# CH32V203K6T6-R0.net
KiCad netlist of a schematic drawn in Altium Designer
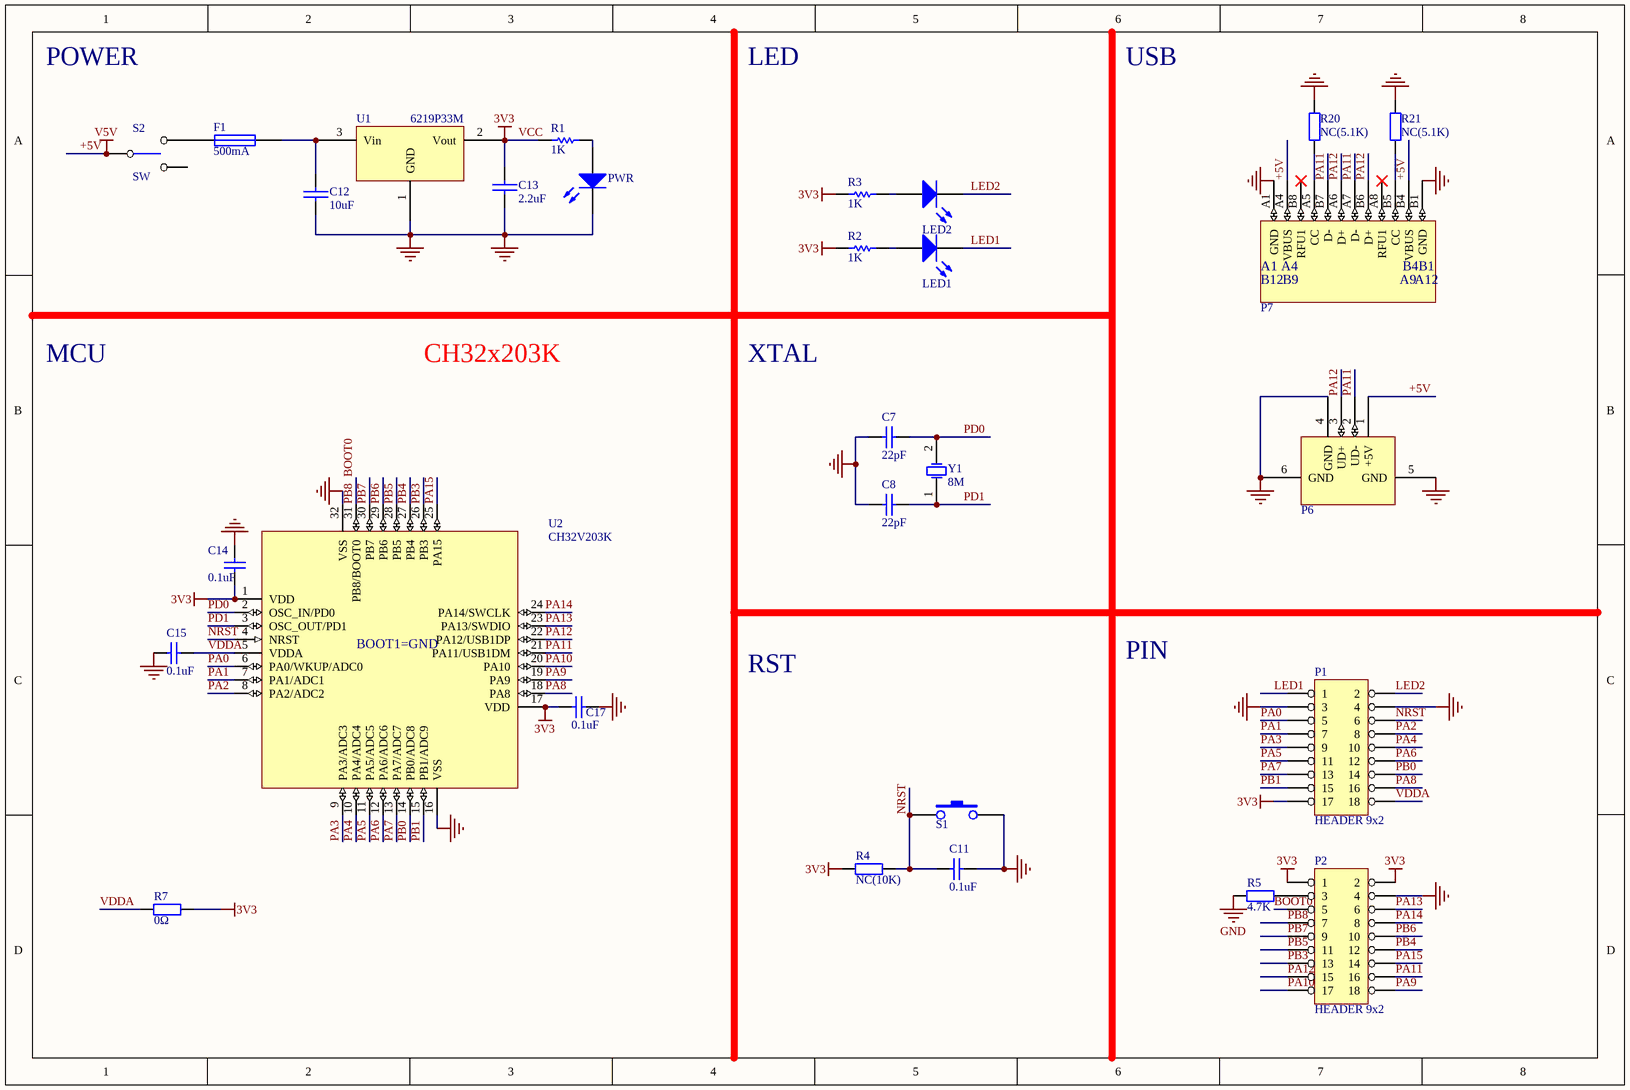
[diagram p0: CH32V203K6T6-R0.SchDoc]

(export (version "E")
  (design (tool "Eeschema 10.0.6"))
  (components
    (comp (ref "C7")
      (value "22pF")
      (footprint "0603_C")
      (description "Capacitor")
      (fields (field (name "PUBLISHER") "Altium Limited"))
      (libsource (lib "*") (part "Cap"))
    )
    (comp (ref "C8")
      (value "22pF")
      (footprint "0603_C")
      (description "Capacitor")
      (fields (field (name "PUBLISHER") "Altium Limited"))
      (libsource (lib "*") (part "Cap"))
    )
    (comp (ref "C11")
      (value "0.1uF")
      (footprint "0603_C")
      (description "Capacitor")
      (fields (field (name "PUBLISHER") "Altium Limited"))
      (libsource (lib "*") (part "Cap"))
    )
    (comp (ref "C12")
      (value "10uF")
      (footprint "3216_C")
      (description "Capacitor")
      (libsource (lib "wch_sch_others") (part "CAP"))
    )
    (comp (ref "C13")
      (value "2.2uF")
      (footprint "0603_C")
      (description "Capacitor")
      (libsource (lib "wch_sch_others") (part "CAP"))
    )
    (comp (ref "C14")
      (value "0.1uF")
      (footprint "0603_C")
      (description "Capacitor")
      (fields (field (name "PUBLISHER") "Altium Limited"))
      (libsource (lib "*") (part "Cap"))
    )
    (comp (ref "C15")
      (value "0.1uF")
      (footprint "0603_C")
      (description "Capacitor")
      (fields (field (name "PUBLISHER") "Altium Limited"))
      (libsource (lib "*") (part "Cap"))
    )
    (comp (ref "C17")
      (value "0.1uF")
      (footprint "0603_C")
      (description "Capacitor")
      (fields (field (name "PUBLISHER") "Altium Limited"))
      (libsource (lib "*") (part "Cap"))
    )
    (comp (ref "F1")
      (value "500mA")
      (footprint "0603")
      (description "Fuse")
      (libsource (lib "*") (part "FUSE1"))
    )
    (comp (ref "LED1")
      (value "LED1   blue")
      (footprint "0603+")
      (description "Typical INFRARED GaAs LED")
      (fields (field (name "PUBLISHER") "Altium Limited"))
      (libsource (lib "*") (part "LED0"))
    )
    (comp (ref "LED2")
      (value "LED2  blue")
      (footprint "0603+")
      (description "Typical INFRARED GaAs LED")
      (fields (field (name "PUBLISHER") "Altium Limited"))
      (libsource (lib "*") (part "LED0"))
    )
    (comp (ref "P1")
      (value "HEADER 9x2")
      (footprint "MYPCB:IDC18-2.54MM")
      (description "Header, 9-Pin, Dual row")
      (libsource (lib "wch_sch_others") (part "HEADER 9x2"))
    )
    (comp (ref "P2")
      (value "HEADER 9x2")
      (footprint "MYPCB:IDC18-2.54MM")
      (description "Header, 9-Pin, Dual row")
      (libsource (lib "wch_sch_others") (part "HEADER 9x2"))
    )
    (comp (ref "P6")
      (value "USB_A")
      (footprint "USBAF")
      (description "USB Port")
      (libsource (lib "*") (part "USB"))
    )
    (comp (ref "P7")
      (value "TYPE-C")
      (footprint "TYPE-C-Receptacle-2.0")
      (libsource (lib "*") (part "TYPE-C1"))
    )
    (comp (ref "PWR")
      (value "POWER  red")
      (footprint "0603+")
      (description "Typical INFRARED GaAs LED")
      (fields (field (name "PUBLISHER") "Altium Limited"))
      (libsource (lib "*") (part "LED0"))
    )
    (comp (ref "R1")
      (value "1K")
      (footprint "0603")
      (description "Semiconductor Resistor")
      (fields (field (name "PUBLISHER") "Altium Limited"))
      (libsource (lib "*") (part "Res Semi"))
    )
    (comp (ref "R2")
      (value "1K")
      (footprint "0603")
      (description "Semiconductor Resistor")
      (fields (field (name "PUBLISHER") "Altium Limited"))
      (libsource (lib "*") (part "Res Semi"))
    )
    (comp (ref "R3")
      (value "1K")
      (footprint "0603")
      (description "Semiconductor Resistor")
      (fields (field (name "PUBLISHER") "Altium Limited"))
      (libsource (lib "*") (part "Res Semi"))
    )
    (comp (ref "R4")
      (value "NC(10K)")
      (footprint "0603")
      (description "Resistor")
      (fields (field (name "PUBLISHER") "Altium Limited"))
      (libsource (lib "") (part "Res2_1"))
    )
    (comp (ref "R5")
      (value "4.7K")
      (footprint "0603")
      (description "Resistor")
      (fields (field (name "PUBLISHER") "Altium Limited"))
      (libsource (lib "*") (part "Res2"))
    )
    (comp (ref "R7")
      (value "0Ω")
      (footprint "0603")
      (description "Resistor")
      (fields (field (name "PUBLISHER") "Altium Limited"))
      (libsource (lib "") (part "Res2_1"))
    )
    (comp (ref "R20")
      (value "NC(5.1K)")
      (footprint "0603")
      (description "Resistor")
      (libsource (lib "Miscellaneous Devices") (part "Res2"))
    )
    (comp (ref "R21")
      (value "NC(5.1K)")
      (footprint "0603")
      (description "Resistor")
      (libsource (lib "Miscellaneous Devices") (part "Res2"))
    )
    (comp (ref "S1") (value "RST") (footprint "SMD_6.1x3.65x2.5mm-KEY") (libsource (lib "*") (part "KEY")))
    (comp (ref "S2") (value "SW") (footprint "KEY2") (libsource (lib "*") (part "SW")))
    (comp (ref "U1")
      (value "6219P33M")
      (footprint "SOT-23")
      (libsource (lib "wch_sch_others") (part "6219P33M"))
    )
    (comp (ref "U2")
      (value "CH32V203K")
      (footprint "LQFP32")
      (description "RISC-V LMD-MCU, 144MHz, USB FS, CAN")
      (libsource (lib "CHXXX") (part "CH32V203K"))
    )
    (comp (ref "Y1")
      (value "8M")
      (footprint "XT_AT49")
      (description "Crystal Oscillator")
      (fields (field (name "PUBLISHER") "Altium Limited"))
      (libsource (lib "*") (part "XTAL"))
    )
  )
  (nets
    (net (code "2") (name "/BOOT0") (class "Default")
      (node (ref "P2") (pin "5") (pinfunction "5_5") (pintype "passive"))
      (node (ref "P2") (pin "7") (pinfunction "7_7") (pintype "passive"))
      (node (ref "U2") (pin "31") (pinfunction "PB8/BOOT0_31") (pintype "bidirectional"))
    )
    (net (code "3") (name "/LED1") (class "Default")
      (node (ref "LED1") (pin "2") (pinfunction "K_2") (pintype "passive"))
      (node (ref "P1") (pin "1") (pinfunction "1_1") (pintype "passive"))
    )
    (net (code "4") (name "/LED2") (class "Default")
      (node (ref "LED2") (pin "2") (pinfunction "K_2") (pintype "passive"))
      (node (ref "P1") (pin "2") (pinfunction "2_2") (pintype "passive"))
    )
    (net (code "5") (name "/NRST") (class "Default")
      (node (ref "C11") (pin "2") (pinfunction "2_2") (pintype "passive"))
      (node (ref "P1") (pin "6") (pinfunction "6_6") (pintype "passive"))
      (node (ref "R4") (pin "1") (pinfunction "1_1") (pintype "passive"))
      (node (ref "S1") (pin "1") (pinfunction "1_1") (pintype "passive"))
      (node (ref "U2") (pin "4") (pinfunction "NRST_4") (pintype "input"))
    )
    (net (code "6") (name "/PA0") (class "Default")
      (node (ref "P1") (pin "5") (pinfunction "5_5") (pintype "passive"))
      (node (ref "U2") (pin "6") (pinfunction "PA0/WKUP/ADC0_6") (pintype "bidirectional"))
    )
    (net (code "7") (name "/PA1") (class "Default")
      (node (ref "P1") (pin "7") (pinfunction "7_7") (pintype "passive"))
      (node (ref "U2") (pin "7") (pinfunction "PA1/ADC1_7") (pintype "bidirectional"))
    )
    (net (code "8") (name "/PA2") (class "Default")
      (node (ref "P1") (pin "8") (pinfunction "8_8") (pintype "passive"))
      (node (ref "U2") (pin "8") (pinfunction "PA2/ADC2_8") (pintype "bidirectional"))
    )
    (net (code "9") (name "/PA3") (class "Default")
      (node (ref "P1") (pin "9") (pinfunction "9_9") (pintype "passive"))
      (node (ref "U2") (pin "9") (pinfunction "PA3/ADC3_9") (pintype "bidirectional"))
    )
    (net (code "10") (name "/PA4") (class "Default")
      (node (ref "P1") (pin "10") (pinfunction "10_10") (pintype "passive"))
      (node (ref "U2") (pin "10") (pinfunction "PA4/ADC4_10") (pintype "bidirectional"))
    )
    (net (code "11") (name "/PA5") (class "Default")
      (node (ref "P1") (pin "11") (pinfunction "11_11") (pintype "passive"))
      (node (ref "U2") (pin "11") (pinfunction "PA5/ADC5_11") (pintype "bidirectional"))
    )
    (net (code "12") (name "/PA6") (class "Default")
      (node (ref "P1") (pin "12") (pinfunction "12_12") (pintype "passive"))
      (node (ref "U2") (pin "12") (pinfunction "PA6/ADC6_12") (pintype "bidirectional"))
    )
    (net (code "13") (name "/PA7") (class "Default")
      (node (ref "P1") (pin "13") (pinfunction "13_13") (pintype "passive"))
      (node (ref "U2") (pin "13") (pinfunction "PA7/ADC7_13") (pintype "bidirectional"))
    )
    (net (code "14") (name "/PA8") (class "Default")
      (node (ref "P1") (pin "16") (pinfunction "16_16") (pintype "passive"))
      (node (ref "U2") (pin "18") (pinfunction "PA8_18") (pintype "bidirectional"))
    )
    (net (code "15") (name "/PA9") (class "Default")
      (node (ref "P2") (pin "18") (pinfunction "18_18") (pintype "passive"))
      (node (ref "U2") (pin "19") (pinfunction "PA9_19") (pintype "bidirectional"))
    )
    (net (code "16") (name "/PA10") (class "Default")
      (node (ref "P2") (pin "17") (pinfunction "17_17") (pintype "passive"))
      (node (ref "U2") (pin "20") (pinfunction "PA10_20") (pintype "bidirectional"))
    )
    (net (code "17") (name "/PA11") (class "Default")
      (node (ref "P2") (pin "16") (pinfunction "16_16") (pintype "passive"))
      (node (ref "P6") (pin "2") (pinfunction "UD-_2") (pintype "bidirectional"))
      (node (ref "P7") (pin "A7") (pinfunction "D-_A7") (pintype "bidirectional"))
      (node (ref "P7") (pin "B7") (pinfunction "D-_B7") (pintype "bidirectional"))
      (node (ref "U2") (pin "21") (pinfunction "PA11/USB1DM_21") (pintype "bidirectional"))
    )
    (net (code "18") (name "/PA12") (class "Default")
      (node (ref "P2") (pin "15") (pinfunction "15_15") (pintype "passive"))
      (node (ref "P6") (pin "3") (pinfunction "UD+_3") (pintype "bidirectional"))
      (node (ref "P7") (pin "A6") (pinfunction "D+_A6") (pintype "bidirectional"))
      (node (ref "P7") (pin "B6") (pinfunction "D+_B6") (pintype "bidirectional"))
      (node (ref "U2") (pin "22") (pinfunction "PA12/USB1DP_22") (pintype "bidirectional"))
    )
    (net (code "19") (name "/PA13") (class "Default")
      (node (ref "P2") (pin "6") (pinfunction "6_6") (pintype "passive"))
      (node (ref "U2") (pin "23") (pinfunction "PA13/SWDIO_23") (pintype "bidirectional"))
    )
    (net (code "20") (name "/PA14") (class "Default")
      (node (ref "P2") (pin "8") (pinfunction "8_8") (pintype "passive"))
      (node (ref "U2") (pin "24") (pinfunction "PA14/SWCLK_24") (pintype "bidirectional"))
    )
    (net (code "21") (name "/PA15") (class "Default")
      (node (ref "P2") (pin "14") (pinfunction "14_14") (pintype "passive"))
      (node (ref "U2") (pin "25") (pinfunction "PA15_25") (pintype "bidirectional"))
    )
    (net (code "22") (name "/PB0") (class "Default")
      (node (ref "P1") (pin "14") (pinfunction "14_14") (pintype "passive"))
      (node (ref "U2") (pin "14") (pinfunction "PB0/ADC8_14") (pintype "bidirectional"))
    )
    (net (code "23") (name "/PB1") (class "Default")
      (node (ref "P1") (pin "15") (pinfunction "15_15") (pintype "passive"))
      (node (ref "U2") (pin "15") (pinfunction "PB1/ADC9_15") (pintype "bidirectional"))
    )
    (net (code "24") (name "/PB3") (class "Default")
      (node (ref "P2") (pin "13") (pinfunction "13_13") (pintype "passive"))
      (node (ref "U2") (pin "26") (pinfunction "PB3_26") (pintype "bidirectional"))
    )
    (net (code "25") (name "/PB4") (class "Default")
      (node (ref "P2") (pin "12") (pinfunction "12_12") (pintype "passive"))
      (node (ref "U2") (pin "27") (pinfunction "PB4_27") (pintype "bidirectional"))
    )
    (net (code "26") (name "/PB5") (class "Default")
      (node (ref "P2") (pin "11") (pinfunction "11_11") (pintype "passive"))
      (node (ref "U2") (pin "28") (pinfunction "PB5_28") (pintype "bidirectional"))
    )
    (net (code "27") (name "/PB6") (class "Default")
      (node (ref "P2") (pin "10") (pinfunction "10_10") (pintype "passive"))
      (node (ref "U2") (pin "29") (pinfunction "PB6_29") (pintype "bidirectional"))
    )
    (net (code "28") (name "/PB7") (class "Default")
      (node (ref "P2") (pin "9") (pinfunction "9_9") (pintype "passive"))
      (node (ref "U2") (pin "30") (pinfunction "PB7_30") (pintype "bidirectional"))
    )
    (net (code "29") (name "/PD0") (class "Default")
      (node (ref "C7") (pin "2") (pinfunction "2_2") (pintype "passive"))
      (node (ref "U2") (pin "2") (pinfunction "OSC_IN/PD0_2") (pintype "bidirectional"))
      (node (ref "Y1") (pin "2") (pinfunction "OSC2_2") (pintype "passive"))
    )
    (net (code "30") (name "/PD1") (class "Default")
      (node (ref "C8") (pin "2") (pinfunction "2_2") (pintype "passive"))
      (node (ref "U2") (pin "3") (pinfunction "OSC_OUT/PD1_3") (pintype "bidirectional"))
      (node (ref "Y1") (pin "1") (pinfunction "OSC1_1") (pintype "passive"))
    )
    (net (code "31") (name "/VDDA") (class "Default")
      (node (ref "C15") (pin "1") (pinfunction "1_1") (pintype "passive"))
      (node (ref "P1") (pin "18") (pinfunction "18_18") (pintype "passive"))
      (node (ref "R7") (pin "2") (pinfunction "2_2") (pintype "passive"))
      (node (ref "U2") (pin "5") (pinfunction "VDDA_5") (pintype "power_in"))
    )
    (net (code "32") (name "3V3") (class "Default")
      (node (ref "C13") (pin "2") (pinfunction "2_2") (pintype "passive"))
      (node (ref "C14") (pin "2") (pinfunction "2_2") (pintype "passive"))
      (node (ref "C17") (pin "1") (pinfunction "1_1") (pintype "passive"))
      (node (ref "P1") (pin "17") (pinfunction "17_17") (pintype "passive"))
      (node (ref "P2") (pin "1") (pinfunction "1_1") (pintype "passive"))
      (node (ref "P2") (pin "2") (pinfunction "2_2") (pintype "passive"))
      (node (ref "R1") (pin "2") (pinfunction "2_2") (pintype "passive"))
      (node (ref "R2") (pin "1") (pinfunction "1_1") (pintype "passive"))
      (node (ref "R3") (pin "1") (pinfunction "1_1") (pintype "passive"))
      (node (ref "R4") (pin "2") (pinfunction "2_2") (pintype "passive"))
      (node (ref "R7") (pin "1") (pinfunction "1_1") (pintype "passive"))
      (node (ref "U1") (pin "2") (pinfunction "Vout_2") (pintype "passive"))
      (node (ref "U2") (pin "1") (pinfunction "VDD_1") (pintype "power_in"))
      (node (ref "U2") (pin "17") (pinfunction "VDD_17") (pintype "power_in"))
    )
    (net (code "33") (name "GND") (class "Default")
      (node (ref "C11") (pin "1") (pinfunction "1_1") (pintype "passive"))
      (node (ref "C12") (pin "2") (pinfunction "2_2") (pintype "passive"))
      (node (ref "C13") (pin "1") (pinfunction "1_1") (pintype "passive"))
      (node (ref "C14") (pin "1") (pinfunction "1_1") (pintype "passive"))
      (node (ref "C15") (pin "2") (pinfunction "2_2") (pintype "passive"))
      (node (ref "C17") (pin "2") (pinfunction "2_2") (pintype "passive"))
      (node (ref "C7") (pin "1") (pinfunction "1_1") (pintype "passive"))
      (node (ref "C8") (pin "1") (pinfunction "1_1") (pintype "passive"))
      (node (ref "P1") (pin "3") (pinfunction "3_3") (pintype "passive"))
      (node (ref "P1") (pin "4") (pinfunction "4_4") (pintype "passive"))
      (node (ref "P2") (pin "4") (pinfunction "4_4") (pintype "passive"))
      (node (ref "P6") (pin "4") (pinfunction "GND_4") (pintype "power_in"))
      (node (ref "P6") (pin "5") (pinfunction "GND_5") (pintype "power_in"))
      (node (ref "P6") (pin "6") (pinfunction "GND_6") (pintype "power_in"))
      (node (ref "P7") (pin "A1") (pinfunction "GND_A1") (pintype "bidirectional"))
      (node (ref "P7") (pin "B1") (pinfunction "GND_B1") (pintype "bidirectional"))
      (node (ref "PWR") (pin "2") (pinfunction "K_2") (pintype "passive"))
      (node (ref "R20") (pin "2") (pinfunction "2_2") (pintype "passive"))
      (node (ref "R21") (pin "2") (pinfunction "2_2") (pintype "passive"))
      (node (ref "R5") (pin "1") (pinfunction "1_1") (pintype "passive"))
      (node (ref "S1") (pin "2") (pinfunction "2_2") (pintype "passive"))
      (node (ref "U1") (pin "1") (pinfunction "GND_1") (pintype "passive"))
      (node (ref "U2") (pin "16") (pinfunction "VSS_16") (pintype "power_in"))
      (node (ref "U2") (pin "32") (pinfunction "VSS_32") (pintype "power_in"))
    )
    (net (code "34") (name "Net-(F1-Pad1)") (class "Default")
      (node (ref "F1") (pin "1") (pinfunction "1_1") (pintype "passive"))
      (node (ref "S2") (pin "3") (pinfunction "3_3") (pintype "passive"))
    )
    (net (code "35") (name "Net-(LED1-A)") (class "Default")
      (node (ref "LED1") (pin "1") (pinfunction "A_1") (pintype "passive"))
      (node (ref "R2") (pin "2") (pinfunction "2_2") (pintype "passive"))
    )
    (net (code "36") (name "Net-(LED2-A)") (class "Default")
      (node (ref "LED2") (pin "1") (pinfunction "A_1") (pintype "passive"))
      (node (ref "R3") (pin "2") (pinfunction "2_2") (pintype "passive"))
    )
    (net (code "37") (name "Net-(P2-Pad3)") (class "Default")
      (node (ref "P2") (pin "3") (pinfunction "3_3") (pintype "passive"))
      (node (ref "R5") (pin "2") (pinfunction "2_2") (pintype "passive"))
    )
    (net (code "38") (name "Net-(P7-CC-PadA5)") (class "Default")
      (node (ref "P7") (pin "A5") (pinfunction "CC_A5") (pintype "bidirectional"))
      (node (ref "R20") (pin "1") (pinfunction "1_1") (pintype "passive"))
    )
    (net (code "39") (name "Net-(P7-CC-PadB5)") (class "Default")
      (node (ref "P7") (pin "B5") (pinfunction "CC_B5") (pintype "bidirectional"))
      (node (ref "R21") (pin "1") (pinfunction "1_1") (pintype "passive"))
    )
    (net (code "40") (name "Net-(PWR-A)") (class "Default")
      (node (ref "PWR") (pin "1") (pinfunction "A_1") (pintype "passive"))
      (node (ref "R1") (pin "1") (pinfunction "1_1") (pintype "passive"))
    )
    (net (code "41") (name "Net-(U1-Vin)") (class "Default")
      (node (ref "C12") (pin "1") (pinfunction "1_1") (pintype "passive"))
      (node (ref "F1") (pin "2") (pinfunction "2_2") (pintype "passive"))
      (node (ref "U1") (pin "3") (pinfunction "Vin_3") (pintype "passive"))
    )
    (net (code "42") (name "V5V") (class "Default")
      (node (ref "P6") (pin "1") (pinfunction "+5V_1") (pintype "power_in"))
      (node (ref "P7") (pin "A4") (pinfunction "VBUS_A4") (pintype "bidirectional"))
      (node (ref "P7") (pin "B4") (pinfunction "VBUS_B4") (pintype "bidirectional"))
      (node (ref "S2") (pin "1") (pinfunction "1_1") (pintype "passive"))
    )
    (net (code "43") (name "unconnected-(P7-RFU1-PadA8)") (class "Default")
      (node (ref "P7") (pin "A8") (pinfunction "RFU1_A8") (pintype "bidirectional+no_connect"))
    )
    (net (code "44") (name "unconnected-(P7-RFU1-PadB8)") (class "Default")
      (node (ref "P7") (pin "B8") (pinfunction "RFU1_B8") (pintype "bidirectional+no_connect"))
    )
    (net (code "45") (name "unconnected-(S2-Pad2)") (class "Default")
      (node (ref "S2") (pin "2") (pinfunction "2_2") (pintype "passive"))
    )
  )
)
